# ledCtrl.net
KiCad netlist of a schematic drawn in EAGLE
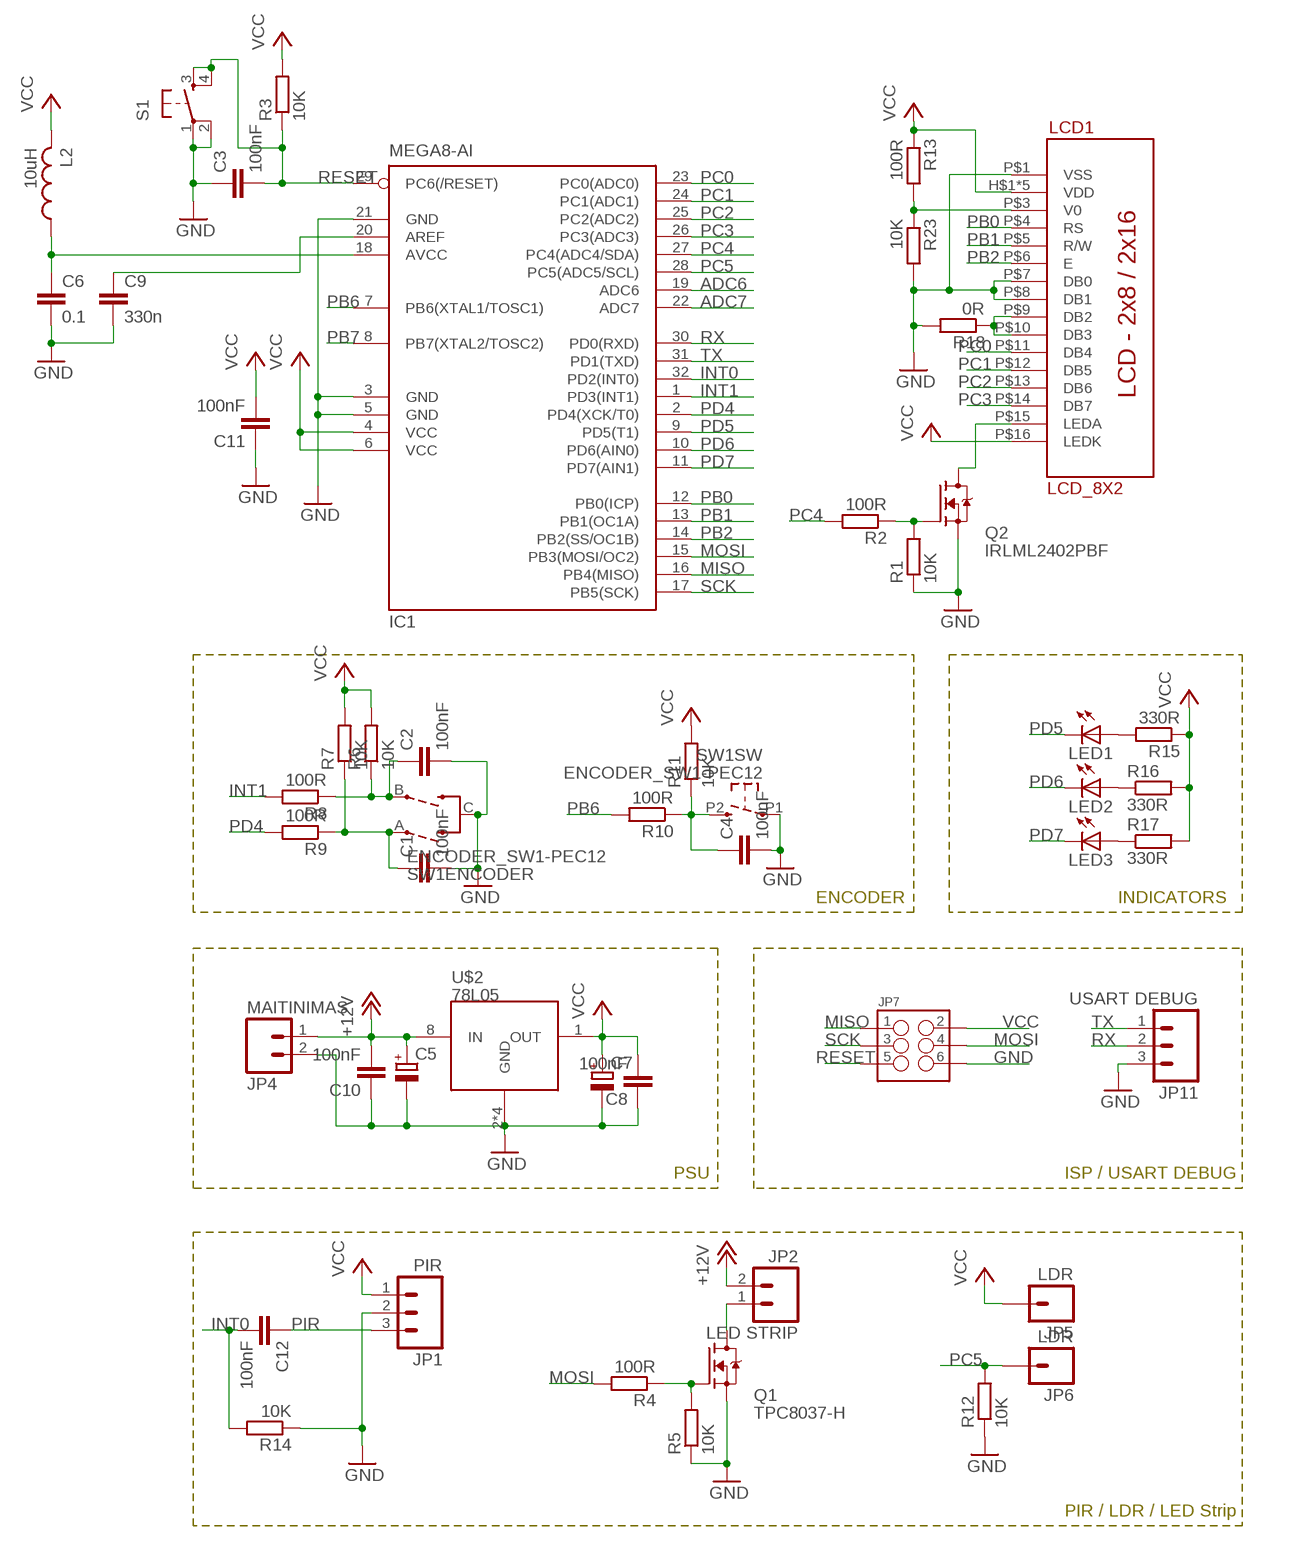
[diagram p0: schematic, sheet 1]

(export (version "E")
  (design (tool "Eeschema 10.0.6"))
  (components
    (comp (ref "C1")
      (value "100nF")
      (footprint "eagle-import:C0805")
      (libsource (lib "eagle-import") (part "C-EUC0805"))
    )
    (comp (ref "C2")
      (value "100nF")
      (footprint "eagle-import:C0805")
      (libsource (lib "eagle-import") (part "C-EUC0805"))
    )
    (comp (ref "C3")
      (value "100nF")
      (footprint "eagle-import:C0805")
      (libsource (lib "eagle-import") (part "C-EUC0805"))
    )
    (comp (ref "C4")
      (value "100nF")
      (footprint "eagle-import:C0805")
      (libsource (lib "eagle-import") (part "C-EUC0805"))
    )
    (comp (ref "C5")
      (value "CPOL-EUSMCC")
      (footprint "eagle-import:SMC_C")
      (libsource (lib "eagle-import") (part "CPOL-EUSMCC"))
    )
    (comp (ref "C6")
      (value "0.1")
      (footprint "eagle-import:C0805K")
      (libsource (lib "eagle-import") (part "C-EUC0805K"))
    )
    (comp (ref "C7")
      (value "CPOL-EUSMCC")
      (footprint "eagle-import:SMC_C")
      (libsource (lib "eagle-import") (part "CPOL-EUSMCC"))
    )
    (comp (ref "C8")
      (value "100nF")
      (footprint "eagle-import:C0805")
      (libsource (lib "eagle-import") (part "C-EUC0805"))
    )
    (comp (ref "C9")
      (value "330n")
      (footprint "eagle-import:C0805")
      (libsource (lib "eagle-import") (part "C-EUC0805"))
    )
    (comp (ref "C10")
      (value "100nF")
      (footprint "eagle-import:C0805")
      (libsource (lib "eagle-import") (part "C-EUC0805"))
    )
    (comp (ref "C11")
      (value "100nF")
      (footprint "eagle-import:C0805")
      (libsource (lib "eagle-import") (part "C-EUC0805"))
    )
    (comp (ref "C12")
      (value "100nF")
      (footprint "eagle-import:C0805")
      (libsource (lib "eagle-import") (part "C-EUC0805"))
    )
    (comp (ref "IC1")
      (value "MEGA8-AI")
      (footprint "eagle-import:TQFP32-08")
      (fields (field (name "MPN") "ATMEGA8-16AU"))
      (libsource (lib "eagle-import") (part "MEGA8-AI"))
    )
    (comp (ref "JP1")
      (value "PIR")
      (footprint "eagle-import:1X03_LOCK")
      (libsource (lib "eagle-import") (part "M03LOCK"))
    )
    (comp (ref "JP2")
      (value "LED STRIP")
      (footprint "eagle-import:SCREWTERMINAL-3.5MM-2-NS")
      (libsource (lib "eagle-import") (part "M023.5MM-NO_SILK"))
    )
    (comp (ref "JP4")
      (value "MAITINIMAS")
      (footprint "eagle-import:SCREWTERMINAL-3.5MM-2-NS")
      (libsource (lib "eagle-import") (part "M023.5MM-NO_SILK"))
    )
    (comp (ref "JP5")
      (value "LDR")
      (footprint "eagle-import:1X01_LONGPAD")
      (libsource (lib "eagle-import") (part "M01PTH_LONGPAD"))
    )
    (comp (ref "JP6")
      (value "LDR")
      (footprint "eagle-import:1X01_LONGPAD")
      (libsource (lib "eagle-import") (part "M01PTH_LONGPAD"))
    )
    (comp (ref "JP7")
      (value "M03X2")
      (footprint "eagle-import:2X3-SHROUDED")
      (libsource (lib "eagle-import") (part "M03X2"))
    )
    (comp (ref "JP11")
      (value "USART DEBUG")
      (footprint "eagle-import:1X03_LOCK")
      (libsource (lib "eagle-import") (part "M03LOCK"))
    )
    (comp (ref "L2")
      (value "10uH")
      (footprint "eagle-import:L2825P")
      (libsource (lib "eagle-import") (part "L-USL2825P"))
    )
    (comp (ref "LCD1")
      (value "LCD_8X2")
      (footprint "eagle-import:LCD_2X8")
      (libsource (lib "eagle-import") (part "LCD_8X2"))
    )
    (comp (ref "LED1")
      (value "LEDCHIP-LED0805")
      (footprint "eagle-import:CHIP-LED0805")
      (libsource (lib "eagle-import") (part "LEDCHIP-LED0805"))
    )
    (comp (ref "LED2")
      (value "LEDCHIP-LED0805")
      (footprint "eagle-import:CHIP-LED0805")
      (libsource (lib "eagle-import") (part "LEDCHIP-LED0805"))
    )
    (comp (ref "LED3")
      (value "LEDCHIP-LED0805")
      (footprint "eagle-import:CHIP-LED0805")
      (libsource (lib "eagle-import") (part "LEDCHIP-LED0805"))
    )
    (comp (ref "Q1")
      (value "TPC8037-H")
      (footprint "eagle-import:SO8")
      (libsource (lib "eagle-import") (part "TPC8037-H"))
    )
    (comp (ref "Q2")
      (value "IRLML2402PBF")
      (footprint "eagle-import:SOT23")
      (libsource (lib "eagle-import") (part "IRLML2402PBF"))
    )
    (comp (ref "R1")
      (value "10K")
      (footprint "eagle-import:M0805")
      (libsource (lib "eagle-import") (part "R-EU_M0805"))
    )
    (comp (ref "R2")
      (value "100R")
      (footprint "eagle-import:M0805")
      (libsource (lib "eagle-import") (part "R-EU_M0805"))
    )
    (comp (ref "R3")
      (value "10K")
      (footprint "eagle-import:M0805")
      (libsource (lib "eagle-import") (part "R-EU_M0805"))
    )
    (comp (ref "R4")
      (value "100R")
      (footprint "eagle-import:M0805")
      (libsource (lib "eagle-import") (part "R-EU_M0805"))
    )
    (comp (ref "R5")
      (value "10K")
      (footprint "eagle-import:M0805")
      (libsource (lib "eagle-import") (part "R-EU_M0805"))
    )
    (comp (ref "R6")
      (value "10K")
      (footprint "eagle-import:M0805")
      (libsource (lib "eagle-import") (part "R-EU_M0805"))
    )
    (comp (ref "R7")
      (value "10K")
      (footprint "eagle-import:M0805")
      (libsource (lib "eagle-import") (part "R-EU_M0805"))
    )
    (comp (ref "R8")
      (value "100R")
      (footprint "eagle-import:M0805")
      (libsource (lib "eagle-import") (part "R-EU_M0805"))
    )
    (comp (ref "R9")
      (value "100R")
      (footprint "eagle-import:M0805")
      (libsource (lib "eagle-import") (part "R-EU_M0805"))
    )
    (comp (ref "R10")
      (value "100R")
      (footprint "eagle-import:M0805")
      (libsource (lib "eagle-import") (part "R-EU_M0805"))
    )
    (comp (ref "R11")
      (value "10K")
      (footprint "eagle-import:M0805")
      (libsource (lib "eagle-import") (part "R-EU_M0805"))
    )
    (comp (ref "R12")
      (value "10K")
      (footprint "eagle-import:M1206")
      (libsource (lib "eagle-import") (part "R-EU_M1206"))
    )
    (comp (ref "R13")
      (value "100R")
      (footprint "eagle-import:M0805")
      (libsource (lib "eagle-import") (part "R-EU_M0805"))
    )
    (comp (ref "R14")
      (value "10K")
      (footprint "eagle-import:M0805")
      (libsource (lib "eagle-import") (part "R-EU_M0805"))
    )
    (comp (ref "R15")
      (value "330R")
      (footprint "eagle-import:M0805")
      (libsource (lib "eagle-import") (part "R-EU_M0805"))
    )
    (comp (ref "R16")
      (value "330R")
      (footprint "eagle-import:M0805")
      (libsource (lib "eagle-import") (part "R-EU_M0805"))
    )
    (comp (ref "R17")
      (value "330R")
      (footprint "eagle-import:M0805")
      (libsource (lib "eagle-import") (part "R-EU_M0805"))
    )
    (comp (ref "R18")
      (value "0R")
      (footprint "eagle-import:M1206")
      (libsource (lib "eagle-import") (part "R-EU_M1206"))
    )
    (comp (ref "R23")
      (value "10K")
      (footprint "eagle-import:M0805")
      (libsource (lib "eagle-import") (part "R-EU_M0805"))
    )
    (comp (ref "S1")
      (value "TAC_SWITCHPTH")
      (footprint "eagle-import:TACTILE-PTH")
      (libsource (lib "eagle-import") (part "TAC_SWITCHPTH"))
    )
    (comp (ref "SW1")
      (value "ENCODER_SW1-PEC12")
      (footprint "eagle-import:PEC12_INCREMENTAL_ENCODER")
      (libsource (lib "eagle-import") (part "ENCODER_SW1-PEC12"))
    )
    (comp (ref "U$2")
      (value "78L05")
      (footprint "eagle-import:SO8")
      (libsource (lib "eagle-import") (part "78L05"))
    )
  )
  (nets
    (net (code "1") (name "+12V") (class "Default")
      (node (ref "C10") (pin "2") (pinfunction "2_2") (pintype "passive"))
      (node (ref "C5") (pin "+") (pinfunction "+_+") (pintype "passive"))
      (node (ref "JP2") (pin "2") (pinfunction "2_2") (pintype "passive"))
      (node (ref "JP4") (pin "1") (pinfunction "1_1") (pintype "passive"))
      (node (ref "U$2") (pin "8") (pinfunction "IN_8") (pintype "bidirectional"))
    )
    (net (code "2") (name "/ADC6") (class "Default")
      (node (ref "IC1") (pin "19") (pinfunction "ADC6_19") (pintype "bidirectional"))
    )
    (net (code "3") (name "/ADC7") (class "Default")
      (node (ref "IC1") (pin "22") (pinfunction "ADC7_22") (pintype "bidirectional"))
    )
    (net (code "4") (name "/INT0") (class "Default")
      (node (ref "C12") (pin "2") (pinfunction "2_2") (pintype "passive"))
      (node (ref "IC1") (pin "32") (pinfunction "PD2(INT0)_32") (pintype "bidirectional"))
      (node (ref "R14") (pin "2") (pinfunction "2_2") (pintype "passive"))
    )
    (net (code "5") (name "/INT1") (class "Default")
      (node (ref "IC1") (pin "1") (pinfunction "PD3(INT1)_1") (pintype "bidirectional"))
      (node (ref "R8") (pin "2") (pinfunction "2_2") (pintype "passive"))
    )
    (net (code "6") (name "/MISO") (class "Default")
      (node (ref "IC1") (pin "16") (pinfunction "PB4(MISO)_16") (pintype "bidirectional"))
      (node (ref "JP7") (pin "1") (pinfunction "1_1") (pintype "bidirectional"))
    )
    (net (code "7") (name "/MOSI") (class "Default")
      (node (ref "IC1") (pin "15") (pinfunction "PB3(MOSI/OC2)_15") (pintype "bidirectional"))
      (node (ref "JP7") (pin "4") (pinfunction "4_4") (pintype "bidirectional"))
      (node (ref "R4") (pin "2") (pinfunction "2_2") (pintype "passive"))
    )
    (net (code "8") (name "/PB0") (class "Default")
      (node (ref "IC1") (pin "12") (pinfunction "PB0(ICP)_12") (pintype "bidirectional"))
      (node (ref "LCD1") (pin "P$4") (pinfunction "RS_P$4") (pintype "bidirectional"))
    )
    (net (code "9") (name "/PB1") (class "Default")
      (node (ref "IC1") (pin "13") (pinfunction "PB1(OC1A)_13") (pintype "bidirectional"))
      (node (ref "LCD1") (pin "P$5") (pinfunction "R/W_P$5") (pintype "bidirectional"))
    )
    (net (code "10") (name "/PB2") (class "Default")
      (node (ref "IC1") (pin "14") (pinfunction "PB2(SS/OC1B)_14") (pintype "bidirectional"))
      (node (ref "LCD1") (pin "P$6") (pinfunction "E_P$6") (pintype "bidirectional"))
    )
    (net (code "11") (name "/PB6") (class "Default")
      (node (ref "IC1") (pin "7") (pinfunction "PB6(XTAL1/TOSC1)_7") (pintype "bidirectional"))
      (node (ref "R10") (pin "2") (pinfunction "2_2") (pintype "passive"))
    )
    (net (code "12") (name "/PB7") (class "Default")
      (node (ref "IC1") (pin "8") (pinfunction "PB7(XTAL2/TOSC2)_8") (pintype "bidirectional"))
    )
    (net (code "13") (name "/PC0") (class "Default")
      (node (ref "IC1") (pin "23") (pinfunction "PC0(ADC0)_23") (pintype "bidirectional"))
      (node (ref "LCD1") (pin "P$11") (pinfunction "DB4_P$11") (pintype "bidirectional"))
    )
    (net (code "14") (name "/PC1") (class "Default")
      (node (ref "IC1") (pin "24") (pinfunction "PC1(ADC1)_24") (pintype "bidirectional"))
      (node (ref "LCD1") (pin "P$12") (pinfunction "DB5_P$12") (pintype "bidirectional"))
    )
    (net (code "15") (name "/PC2") (class "Default")
      (node (ref "IC1") (pin "25") (pinfunction "PC2(ADC2)_25") (pintype "bidirectional"))
      (node (ref "LCD1") (pin "P$13") (pinfunction "DB6_P$13") (pintype "bidirectional"))
    )
    (net (code "16") (name "/PC3") (class "Default")
      (node (ref "IC1") (pin "26") (pinfunction "PC3(ADC3)_26") (pintype "bidirectional"))
      (node (ref "LCD1") (pin "P$14") (pinfunction "DB7_P$14") (pintype "bidirectional"))
    )
    (net (code "17") (name "/PC4") (class "Default")
      (node (ref "IC1") (pin "27") (pinfunction "PC4(ADC4/SDA)_27") (pintype "bidirectional"))
      (node (ref "R2") (pin "2") (pinfunction "2_2") (pintype "passive"))
    )
    (net (code "18") (name "/PC5") (class "Default")
      (node (ref "IC1") (pin "28") (pinfunction "PC5(ADC5/SCL)_28") (pintype "bidirectional"))
      (node (ref "JP6") (pin "1") (pinfunction "1_1") (pintype "passive"))
      (node (ref "R12") (pin "2") (pinfunction "2_2") (pintype "passive"))
    )
    (net (code "19") (name "/PD4") (class "Default")
      (node (ref "IC1") (pin "2") (pinfunction "PD4(XCK/T0)_2") (pintype "bidirectional"))
      (node (ref "R9") (pin "2") (pinfunction "2_2") (pintype "passive"))
    )
    (net (code "20") (name "/PD5") (class "Default")
      (node (ref "IC1") (pin "9") (pinfunction "PD5(T1)_9") (pintype "bidirectional"))
      (node (ref "LED1") (pin "C") (pinfunction "C_C") (pintype "passive"))
    )
    (net (code "21") (name "/PD6") (class "Default")
      (node (ref "IC1") (pin "10") (pinfunction "PD6(AIN0)_10") (pintype "bidirectional"))
      (node (ref "LED2") (pin "C") (pinfunction "C_C") (pintype "passive"))
    )
    (net (code "22") (name "/PD7") (class "Default")
      (node (ref "IC1") (pin "11") (pinfunction "PD7(AIN1)_11") (pintype "bidirectional"))
      (node (ref "LED3") (pin "C") (pinfunction "C_C") (pintype "passive"))
    )
    (net (code "23") (name "/PIR") (class "Default")
      (node (ref "C12") (pin "1") (pinfunction "1_1") (pintype "passive"))
      (node (ref "JP1") (pin "3") (pinfunction "3_3") (pintype "passive"))
    )
    (net (code "24") (name "/RESET") (class "Default")
      (node (ref "C3") (pin "2") (pinfunction "2_2") (pintype "passive"))
      (node (ref "IC1") (pin "29") (pinfunction "PC6(/RESET)_29") (pintype "bidirectional"))
      (node (ref "JP7") (pin "5") (pinfunction "5_5") (pintype "bidirectional"))
      (node (ref "R3") (pin "1") (pinfunction "1_1") (pintype "passive"))
      (node (ref "S1") (pin "3") (pinfunction "3_3") (pintype "passive"))
      (node (ref "S1") (pin "4") (pinfunction "4_4") (pintype "passive"))
    )
    (net (code "25") (name "/RX") (class "Default")
      (node (ref "IC1") (pin "30") (pinfunction "PD0(RXD)_30") (pintype "bidirectional"))
      (node (ref "JP11") (pin "2") (pinfunction "2_2") (pintype "passive"))
    )
    (net (code "26") (name "/SCK") (class "Default")
      (node (ref "IC1") (pin "17") (pinfunction "PB5(SCK)_17") (pintype "bidirectional"))
      (node (ref "JP7") (pin "3") (pinfunction "3_3") (pintype "bidirectional"))
    )
    (net (code "27") (name "/TX") (class "Default")
      (node (ref "IC1") (pin "31") (pinfunction "PD1(TXD)_31") (pintype "bidirectional"))
      (node (ref "JP11") (pin "1") (pinfunction "1_1") (pintype "passive"))
    )
    (net (code "28") (name "GND") (class "Default")
      (node (ref "C1") (pin "2") (pinfunction "2_2") (pintype "passive"))
      (node (ref "C10") (pin "1") (pinfunction "1_1") (pintype "passive"))
      (node (ref "C11") (pin "1") (pinfunction "1_1") (pintype "passive"))
      (node (ref "C2") (pin "2") (pinfunction "2_2") (pintype "passive"))
      (node (ref "C3") (pin "1") (pinfunction "1_1") (pintype "passive"))
      (node (ref "C4") (pin "2") (pinfunction "2_2") (pintype "passive"))
      (node (ref "C5") (pin "-") (pinfunction "-_-") (pintype "passive"))
      (node (ref "C6") (pin "2") (pinfunction "2_2") (pintype "passive"))
      (node (ref "C7") (pin "-") (pinfunction "-_-") (pintype "passive"))
      (node (ref "C8") (pin "1") (pinfunction "1_1") (pintype "passive"))
      (node (ref "C9") (pin "2") (pinfunction "2_2") (pintype "passive"))
      (node (ref "IC1") (pin "21") (pinfunction "GND_21") (pintype "power_in"))
      (node (ref "IC1") (pin "3") (pinfunction "GND_3") (pintype "power_in"))
      (node (ref "IC1") (pin "5") (pinfunction "GND_5") (pintype "power_in"))
      (node (ref "JP1") (pin "2") (pinfunction "2_2") (pintype "passive"))
      (node (ref "JP11") (pin "3") (pinfunction "3_3") (pintype "passive"))
      (node (ref "JP4") (pin "2") (pinfunction "2_2") (pintype "passive"))
      (node (ref "JP7") (pin "6") (pinfunction "6_6") (pintype "bidirectional"))
      (node (ref "LCD1") (pin "P$1") (pinfunction "VSS_P$1") (pintype "power_in"))
      (node (ref "LCD1") (pin "P$7") (pinfunction "DB0_P$7") (pintype "bidirectional"))
      (node (ref "LCD1") (pin "P$8") (pinfunction "DB1_P$8") (pintype "bidirectional"))
      (node (ref "Q1") (pin "1") (pinfunction "S_1") (pintype "passive"))
      (node (ref "Q1") (pin "2") (pinfunction "S_2") (pintype "passive"))
      (node (ref "Q1") (pin "3") (pinfunction "S_3") (pintype "passive"))
      (node (ref "Q2") (pin "2") (pinfunction "S_2") (pintype "passive"))
      (node (ref "R1") (pin "1") (pinfunction "1_1") (pintype "passive"))
      (node (ref "R12") (pin "1") (pinfunction "1_1") (pintype "passive"))
      (node (ref "R14") (pin "1") (pinfunction "1_1") (pintype "passive"))
      (node (ref "R18") (pin "2") (pinfunction "2_2") (pintype "passive"))
      (node (ref "R23") (pin "2") (pinfunction "2_2") (pintype "passive"))
      (node (ref "R5") (pin "1") (pinfunction "1_1") (pintype "passive"))
      (node (ref "S1") (pin "1") (pinfunction "1_1") (pintype "passive"))
      (node (ref "S1") (pin "2") (pinfunction "2_2") (pintype "passive"))
      (node (ref "SW1") (pin "C") (pinfunction "C_C") (pintype "passive"))
      (node (ref "SW1") (pin "P1") (pinfunction "1_P1") (pintype "passive"))
      (node (ref "U$2") (pin "2") (pinfunction "GND_2") (pintype "bidirectional"))
      (node (ref "U$2") (pin "3") (pinfunction "GND_3") (pintype "bidirectional"))
      (node (ref "U$2") (pin "6") (pinfunction "GND_6") (pintype "bidirectional"))
      (node (ref "U$2") (pin "7") (pinfunction "GND_7") (pintype "bidirectional"))
    )
    (net (code "29") (name "Net-(C1-Pad1)") (class "Default")
      (node (ref "C1") (pin "1") (pinfunction "1_1") (pintype "passive"))
      (node (ref "R7") (pin "1") (pinfunction "1_1") (pintype "passive"))
      (node (ref "R9") (pin "1") (pinfunction "1_1") (pintype "passive"))
      (node (ref "SW1") (pin "A") (pinfunction "A_A") (pintype "passive"))
    )
    (net (code "30") (name "Net-(C2-Pad1)") (class "Default")
      (node (ref "C2") (pin "1") (pinfunction "1_1") (pintype "passive"))
      (node (ref "R6") (pin "1") (pinfunction "1_1") (pintype "passive"))
      (node (ref "R8") (pin "1") (pinfunction "1_1") (pintype "passive"))
      (node (ref "SW1") (pin "B") (pinfunction "B_B") (pintype "passive"))
    )
    (net (code "31") (name "Net-(IC1-AREF)") (class "Default")
      (node (ref "C9") (pin "1") (pinfunction "1_1") (pintype "passive"))
      (node (ref "IC1") (pin "20") (pinfunction "AREF_20") (pintype "passive"))
    )
    (net (code "32") (name "Net-(IC1-AVCC)") (class "Default")
      (node (ref "C6") (pin "1") (pinfunction "1_1") (pintype "passive"))
      (node (ref "IC1") (pin "18") (pinfunction "AVCC_18") (pintype "power_in"))
      (node (ref "L2") (pin "1") (pinfunction "1_1") (pintype "passive"))
    )
    (net (code "33") (name "Net-(JP2-Pad1)") (class "Default")
      (node (ref "JP2") (pin "1") (pinfunction "1_1") (pintype "passive"))
      (node (ref "Q1") (pin "5") (pinfunction "D_5") (pintype "passive"))
      (node (ref "Q1") (pin "6") (pinfunction "D_6") (pintype "passive"))
      (node (ref "Q1") (pin "7") (pinfunction "D_7") (pintype "passive"))
      (node (ref "Q1") (pin "8") (pinfunction "D_8") (pintype "passive"))
    )
    (net (code "34") (name "Net-(LCD1-DB2)") (class "Default")
      (node (ref "LCD1") (pin "P$10") (pinfunction "DB3_P$10") (pintype "bidirectional"))
      (node (ref "LCD1") (pin "P$9") (pinfunction "DB2_P$9") (pintype "bidirectional"))
      (node (ref "R18") (pin "1") (pinfunction "1_1") (pintype "passive"))
    )
    (net (code "35") (name "Net-(LCD1-LEDA)") (class "Default")
      (node (ref "LCD1") (pin "P$15") (pinfunction "LEDA_P$15") (pintype "power_in"))
      (node (ref "Q2") (pin "3") (pinfunction "D_3") (pintype "passive"))
    )
    (net (code "36") (name "Net-(LCD1-V0)") (class "Default")
      (node (ref "LCD1") (pin "P$3") (pinfunction "V0_P$3") (pintype "bidirectional"))
      (node (ref "R13") (pin "2") (pinfunction "2_2") (pintype "passive"))
      (node (ref "R23") (pin "1") (pinfunction "1_1") (pintype "passive"))
    )
    (net (code "37") (name "Net-(LED1-PadA)") (class "Default")
      (node (ref "LED1") (pin "A") (pinfunction "A_A") (pintype "passive"))
      (node (ref "R15") (pin "2") (pinfunction "2_2") (pintype "passive"))
    )
    (net (code "38") (name "Net-(LED2-PadA)") (class "Default")
      (node (ref "LED2") (pin "A") (pinfunction "A_A") (pintype "passive"))
      (node (ref "R16") (pin "1") (pinfunction "1_1") (pintype "passive"))
    )
    (net (code "39") (name "Net-(LED3-PadA)") (class "Default")
      (node (ref "LED3") (pin "A") (pinfunction "A_A") (pintype "passive"))
      (node (ref "R17") (pin "1") (pinfunction "1_1") (pintype "passive"))
    )
    (net (code "40") (name "Net-(Q1-G)") (class "Default")
      (node (ref "Q1") (pin "4") (pinfunction "G_4") (pintype "passive"))
      (node (ref "R4") (pin "1") (pinfunction "1_1") (pintype "passive"))
      (node (ref "R5") (pin "2") (pinfunction "2_2") (pintype "passive"))
    )
    (net (code "41") (name "Net-(Q2-G)") (class "Default")
      (node (ref "Q2") (pin "1") (pinfunction "G_1") (pintype "passive"))
      (node (ref "R1") (pin "2") (pinfunction "2_2") (pintype "passive"))
      (node (ref "R2") (pin "1") (pinfunction "1_1") (pintype "passive"))
    )
    (net (code "42") (name "Net-(SW1B-2)") (class "Default")
      (node (ref "C4") (pin "1") (pinfunction "1_1") (pintype "passive"))
      (node (ref "R10") (pin "1") (pinfunction "1_1") (pintype "passive"))
      (node (ref "R11") (pin "1") (pinfunction "1_1") (pintype "passive"))
      (node (ref "SW1") (pin "P2") (pinfunction "2_P2") (pintype "passive"))
    )
    (net (code "43") (name "VCC") (class "Default")
      (node (ref "C11") (pin "2") (pinfunction "2_2") (pintype "passive"))
      (node (ref "C7") (pin "+") (pinfunction "+_+") (pintype "passive"))
      (node (ref "C8") (pin "2") (pinfunction "2_2") (pintype "passive"))
      (node (ref "IC1") (pin "4") (pinfunction "VCC_4") (pintype "power_in"))
      (node (ref "IC1") (pin "6") (pinfunction "VCC_6") (pintype "power_in"))
      (node (ref "JP1") (pin "1") (pinfunction "1_1") (pintype "passive"))
      (node (ref "JP5") (pin "1") (pinfunction "1_1") (pintype "passive"))
      (node (ref "JP7") (pin "2") (pinfunction "2_2") (pintype "bidirectional"))
      (node (ref "L2") (pin "2") (pinfunction "2_2") (pintype "passive"))
      (node (ref "LCD1") (pin "H$1") (pinfunction "VDD_H$1") (pintype "power_in"))
      (node (ref "LCD1") (pin "H$2") (pinfunction "VDD_H$2") (pintype "power_in"))
      (node (ref "LCD1") (pin "H$3") (pinfunction "VDD_H$3") (pintype "power_in"))
      (node (ref "LCD1") (pin "H$4") (pinfunction "VDD_H$4") (pintype "power_in"))
      (node (ref "LCD1") (pin "P$16") (pinfunction "LEDK_P$16") (pintype "power_in"))
      (node (ref "LCD1") (pin "P$2") (pinfunction "VDD_P$2") (pintype "power_in"))
      (node (ref "R11") (pin "2") (pinfunction "2_2") (pintype "passive"))
      (node (ref "R13") (pin "1") (pinfunction "1_1") (pintype "passive"))
      (node (ref "R15") (pin "1") (pinfunction "1_1") (pintype "passive"))
      (node (ref "R16") (pin "2") (pinfunction "2_2") (pintype "passive"))
      (node (ref "R17") (pin "2") (pinfunction "2_2") (pintype "passive"))
      (node (ref "R3") (pin "2") (pinfunction "2_2") (pintype "passive"))
      (node (ref "R6") (pin "2") (pinfunction "2_2") (pintype "passive"))
      (node (ref "R7") (pin "2") (pinfunction "2_2") (pintype "passive"))
      (node (ref "U$2") (pin "1") (pinfunction "OUT_1") (pintype "bidirectional"))
    )
  )
)
